# SparkFun-NEO-F9P.net
KiCad netlist of a schematic drawn in EAGLE
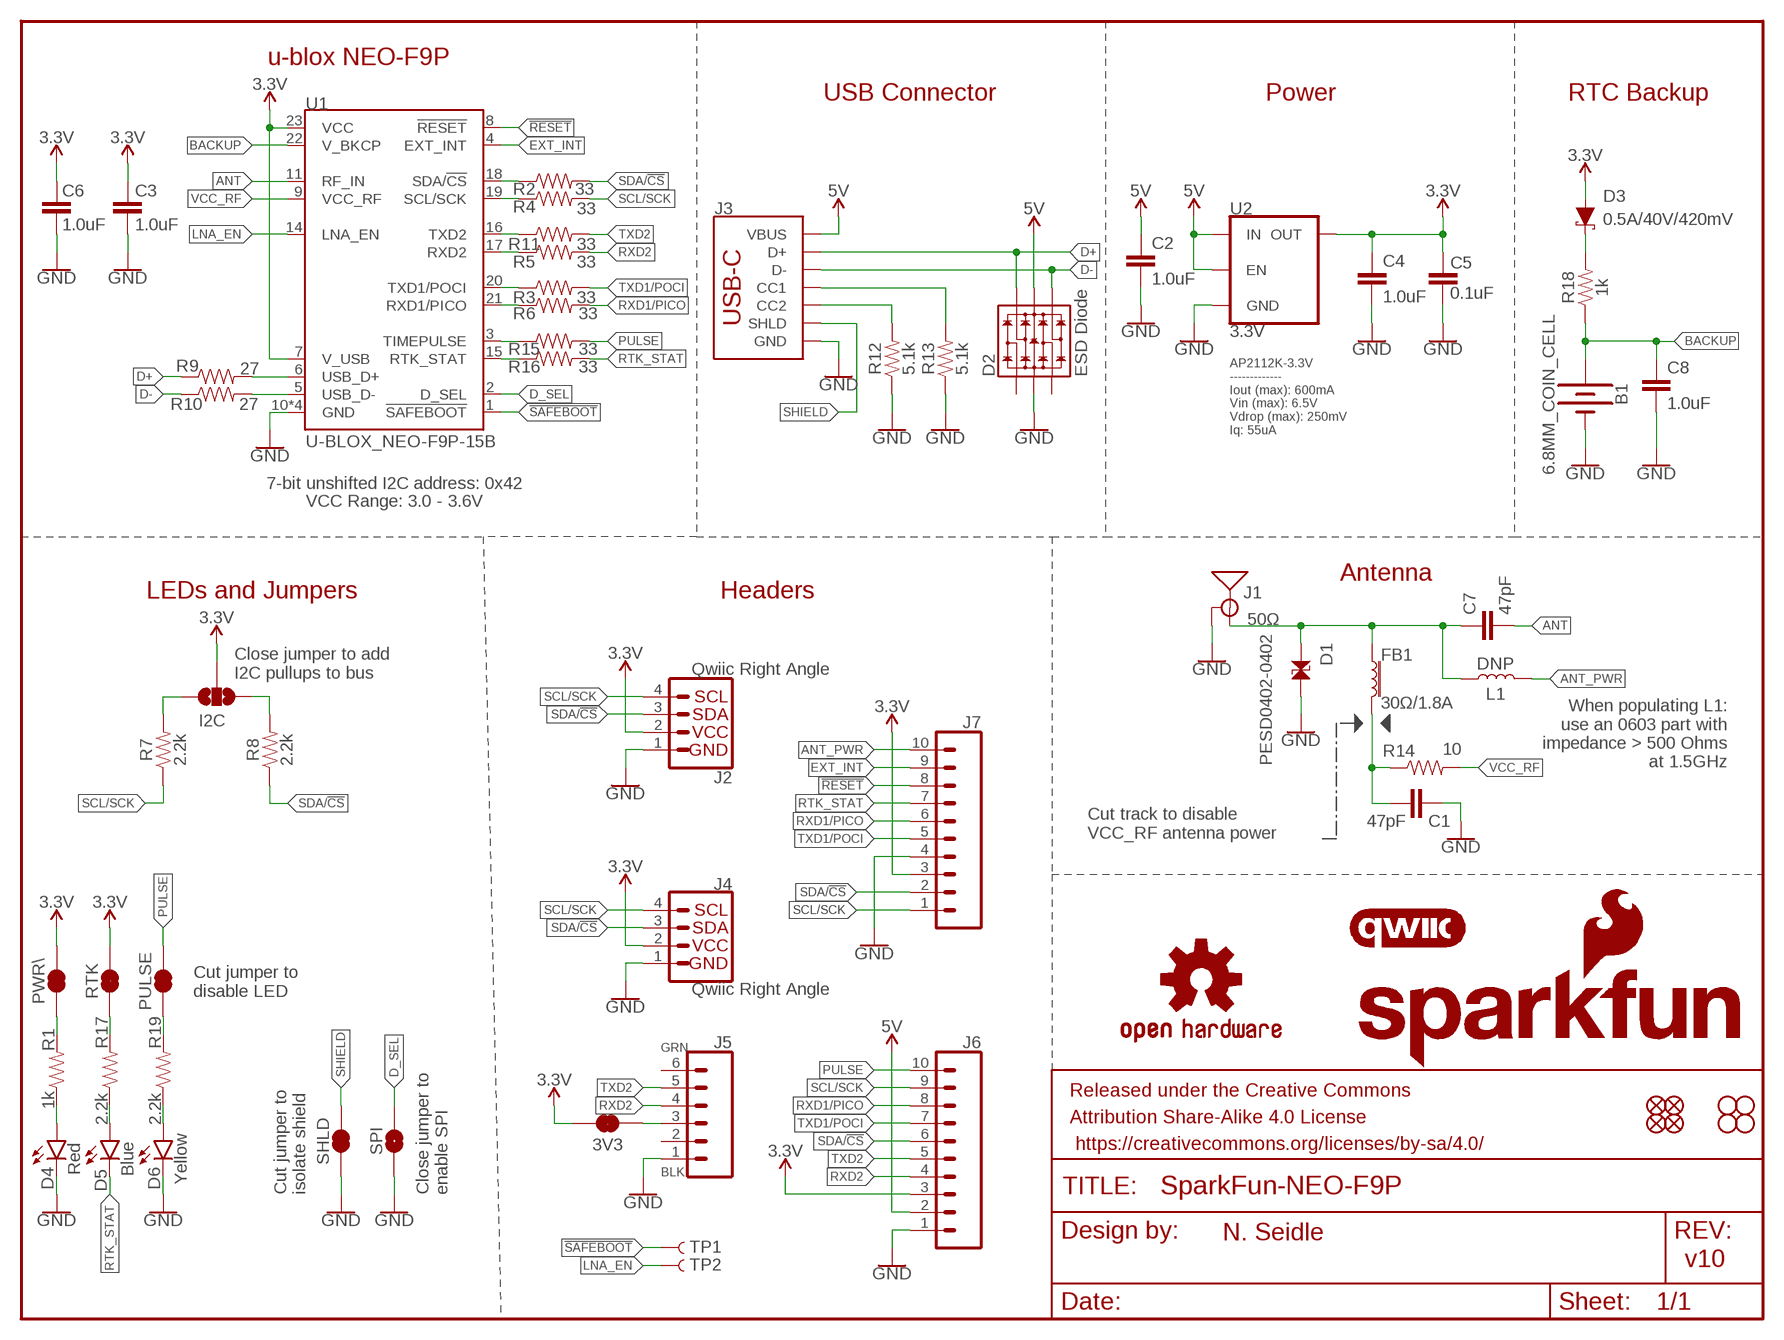
[diagram p0: schematic, sheet 1]

(export (version "E")
  (design (tool "Eeschema 10.0.6"))
  (components
    (comp (ref "3V3")
      (value "JUMPER-SMT_2_NC_TRACE_SILK")
      (footprint "eagle-import:SMT-JUMPER_2_NC_TRACE_SILK")
      (libsource (lib "eagle-import") (part "JUMPER-SMT_2_NC_TRACE_SILK"))
    )
    (comp (ref "B1")
      (value "6.8MM_COIN_CELL")
      (footprint "eagle-import:ML414H_IV01E")
      (libsource (lib "eagle-import") (part "ML414H_IV01E_BATTERY"))
    )
    (comp (ref "C1")
      (value "47pF")
      (footprint "eagle-import:0603")
      (libsource (lib "eagle-import") (part "47PF-0603-50V-5%"))
    )
    (comp (ref "C2")
      (value "1.0uF")
      (footprint "eagle-import:0603")
      (libsource (lib "eagle-import") (part "1.0UF-0603-16V-10%"))
    )
    (comp (ref "C3")
      (value "1.0uF")
      (footprint "eagle-import:0603")
      (libsource (lib "eagle-import") (part "1.0UF-0603-16V-10%"))
    )
    (comp (ref "C4")
      (value "1.0uF")
      (footprint "eagle-import:0603")
      (libsource (lib "eagle-import") (part "1.0UF-0603-16V-10%"))
    )
    (comp (ref "C5")
      (value "0.1uF")
      (footprint "eagle-import:0603")
      (libsource (lib "eagle-import") (part "0.1UF-0603-25V-(+80/-20%)"))
    )
    (comp (ref "C6")
      (value "1.0uF")
      (footprint "eagle-import:0603")
      (libsource (lib "eagle-import") (part "1.0UF-0603-16V-10%"))
    )
    (comp (ref "C7")
      (value "47pF")
      (footprint "eagle-import:0603")
      (libsource (lib "eagle-import") (part "47PF-0603-50V-5%"))
    )
    (comp (ref "C8")
      (value "1.0uF")
      (footprint "eagle-import:0603")
      (libsource (lib "eagle-import") (part "1.0UF-0603-16V-10%-X7R"))
    )
    (comp (ref "D1")
      (value "PESD0402-0402")
      (footprint "eagle-import:0402")
      (fields
        (field (name "DIGIKEY_PART") "PESD0402-140CT-ND")
        (field (name "MOUSE_PART") "650-PESD0402-140")
      )
      (libsource (lib "eagle-import") (part "PESD0402-0402"))
    )
    (comp (ref "D2")
      (value "ESD Diode")
      (footprint "eagle-import:SOT-23-6")
      (libsource (lib "eagle-import") (part "TVS_DIODE_ARRAY_DT1042-04SO-7"))
    )
    (comp (ref "D3")
      (value "0.5A/40V/420mV")
      (footprint "eagle-import:SOD-323")
      (libsource (lib "eagle-import") (part "DIODE-SCHOTTKY-PMEG4005EJ"))
    )
    (comp (ref "D4")
      (value "Red")
      (footprint "eagle-import:LED-0603")
      (libsource (lib "eagle-import") (part "LED-RED0603"))
    )
    (comp (ref "D5")
      (value "Blue")
      (footprint "eagle-import:LED-0603")
      (libsource (lib "eagle-import") (part "LED-BLUE0603"))
    )
    (comp (ref "D6")
      (value "Yellow")
      (footprint "eagle-import:LED-0603")
      (libsource (lib "eagle-import") (part "LED-YELLOW0603"))
    )
    (comp (ref "FB1")
      (value "30Ω/1.8A")
      (footprint "eagle-import:0603")
      (libsource (lib "eagle-import") (part "FERRITE_BEAD-0603"))
    )
    (comp (ref "FRAME1")
      (value "FRAME-LETTER")
      (footprint "eagle-import:CREATIVE_COMMONS")
      (libsource (lib "eagle-import") (part "FRAME-LETTER"))
    )
    (comp (ref "I2C")
      (value "JUMPER-SMT_3_NO_SILK")
      (footprint "eagle-import:SMT-JUMPER_3_NO_SILK")
      (libsource (lib "eagle-import") (part "JUMPER-SMT_3_NO_SILK"))
    )
    (comp (ref "J1")
      (value "ANTENNA-SMA-GROUNDEDEDGE_SMA")
      (footprint "eagle-import:SMA-EDGE")
      (libsource (lib "eagle-import") (part "ANTENNA-SMA-GROUNDEDEDGE_SMA"))
    )
    (comp (ref "J2")
      (value "Qwiic Right Angle")
      (footprint "eagle-import:JST04_1MM_RA")
      (libsource (lib "eagle-import") (part "I2C_STANDARDQWIIC"))
    )
    (comp (ref "J3")
      (value "USB_C_2-LAYER_PADS")
      (footprint "eagle-import:USB-C-16P-2LAYER-PADS")
      (libsource (lib "eagle-import") (part "USB_C_2-LAYER_PADS"))
    )
    (comp (ref "J4")
      (value "Qwiic Right Angle")
      (footprint "eagle-import:JST04_1MM_RA")
      (libsource (lib "eagle-import") (part "I2C_STANDARDQWIIC"))
    )
    (comp (ref "J5")
      (value "CONN_06NO_SILK_FEMALE_PTH")
      (footprint "eagle-import:1X06_NO_SILK")
      (libsource (lib "eagle-import") (part "CONN_06NO_SILK_FEMALE_PTH"))
    )
    (comp (ref "J6")
      (value "CONN_10NO_SILK_PTH_FEMALE")
      (footprint "eagle-import:1X10_NO_SILK")
      (libsource (lib "eagle-import") (part "CONN_10NO_SILK_PTH_FEMALE"))
    )
    (comp (ref "J7")
      (value "CONN_10NO_SILK_PTH_FEMALE")
      (footprint "eagle-import:1X10_NO_SILK")
      (libsource (lib "eagle-import") (part "CONN_10NO_SILK_PTH_FEMALE"))
    )
    (comp (ref "JP21")
      (value "FIDUCIALUFIDUCIAL")
      (footprint "eagle-import:MICRO-FIDUCIAL")
      (libsource (lib "eagle-import") (part "FIDUCIALUFIDUCIAL"))
    )
    (comp (ref "JP31")
      (value "STAND-OFF")
      (footprint "eagle-import:STAND-OFF")
      (libsource (lib "eagle-import") (part "STAND-OFF"))
    )
    (comp (ref "JP41")
      (value "STAND-OFF")
      (footprint "eagle-import:STAND-OFF")
      (libsource (lib "eagle-import") (part "STAND-OFF"))
    )
    (comp (ref "JP61")
      (value "FIDUCIALUFIDUCIAL")
      (footprint "eagle-import:MICRO-FIDUCIAL")
      (libsource (lib "eagle-import") (part "FIDUCIALUFIDUCIAL"))
    )
    (comp (ref "JP71")
      (value "FIDUCIALUFIDUCIAL")
      (footprint "eagle-import:MICRO-FIDUCIAL")
      (libsource (lib "eagle-import") (part "FIDUCIALUFIDUCIAL"))
    )
    (comp (ref "JP81")
      (value "FIDUCIALUFIDUCIAL")
      (footprint "eagle-import:MICRO-FIDUCIAL")
      (libsource (lib "eagle-import") (part "FIDUCIALUFIDUCIAL"))
    )
    (comp (ref "JP91")
      (value "STAND-OFF")
      (footprint "eagle-import:STAND-OFF")
      (libsource (lib "eagle-import") (part "STAND-OFF"))
    )
    (comp (ref "JP101")
      (value "STAND-OFF")
      (footprint "eagle-import:STAND-OFF")
      (libsource (lib "eagle-import") (part "STAND-OFF"))
    )
    (comp (ref "L1")
      (value "DNP")
      (footprint "eagle-import:0603_NO-CREAM")
      (libsource (lib "eagle-import") (part "DNP-0603_NO-CREAM"))
    )
    (comp (ref "LOGO2")
      (value "SFE_LOGO_NAME_FLAME.1_INCH")
      (footprint "eagle-import:SFE_LOGO_NAME_FLAME_.1")
      (libsource (lib "eagle-import") (part "SFE_LOGO_NAME_FLAME.1_INCH"))
    )
    (comp (ref "LOGO3")
      (value "SFE_LOGO_NAME_FLAME7_MM")
      (footprint "eagle-import:SFE_LOGO_NAME_FLAME_7MM")
      (libsource (lib "eagle-import") (part "SFE_LOGO_NAME_FLAME7_MM"))
    )
    (comp (ref "LOGO4")
      (value "OSHW-LOGOS")
      (footprint "eagle-import:OSHW-LOGO-S")
      (libsource (lib "eagle-import") (part "OSHW-LOGOS"))
    )
    (comp (ref "LOGO5")
      (value "QWIIC_LOGO_5MM")
      (footprint "eagle-import:QWIIC_5MM")
      (libsource (lib "eagle-import") (part "QWIIC_LOGO_5MM"))
    )
    (comp (ref "PULSE")
      (value "JUMPER-SMT_2_NC_TRACE_SILK")
      (footprint "eagle-import:SMT-JUMPER_2_NC_TRACE_SILK")
      (libsource (lib "eagle-import") (part "JUMPER-SMT_2_NC_TRACE_SILK"))
    )
    (comp (ref "PWR\\")
      (value "JUMPER-SMT_2_NC_TRACE_SILK")
      (footprint "eagle-import:SMT-JUMPER_2_NC_TRACE_SILK")
      (libsource (lib "eagle-import") (part "JUMPER-SMT_2_NC_TRACE_SILK"))
    )
    (comp (ref "R1")
      (value "1k")
      (footprint "eagle-import:0603")
      (libsource (lib "eagle-import") (part "1KOHM-0603-1/10W-1%"))
    )
    (comp (ref "R2")
      (value "33")
      (footprint "eagle-import:0603")
      (libsource (lib "eagle-import") (part "33OHM-0603-1/10W-1%"))
    )
    (comp (ref "R3")
      (value "33")
      (footprint "eagle-import:0603")
      (libsource (lib "eagle-import") (part "33OHM-0603-1/10W-1%"))
    )
    (comp (ref "R4")
      (value "33")
      (footprint "eagle-import:0603")
      (libsource (lib "eagle-import") (part "33OHM-0603-1/10W-1%"))
    )
    (comp (ref "R5")
      (value "33")
      (footprint "eagle-import:0603")
      (libsource (lib "eagle-import") (part "33OHM-0603-1/10W-1%"))
    )
    (comp (ref "R6")
      (value "33")
      (footprint "eagle-import:0603")
      (libsource (lib "eagle-import") (part "33OHM-0603-1/10W-1%"))
    )
    (comp (ref "R7")
      (value "2.2k")
      (footprint "eagle-import:0603")
      (libsource (lib "eagle-import") (part "2.2KOHM-0603-1/10W-1%"))
    )
    (comp (ref "R8")
      (value "2.2k")
      (footprint "eagle-import:0603")
      (libsource (lib "eagle-import") (part "2.2KOHM-0603-1/10W-1%"))
    )
    (comp (ref "R9")
      (value "27")
      (footprint "eagle-import:0603")
      (libsource (lib "eagle-import") (part "27OHM-0603-1/10W-1%"))
    )
    (comp (ref "R10")
      (value "27")
      (footprint "eagle-import:0603")
      (libsource (lib "eagle-import") (part "27OHM-0603-1/10W-1%"))
    )
    (comp (ref "R11")
      (value "33")
      (footprint "eagle-import:0603")
      (libsource (lib "eagle-import") (part "33OHM-0603-1/10W-1%"))
    )
    (comp (ref "R12")
      (value "5.1k")
      (footprint "eagle-import:0603")
      (libsource (lib "eagle-import") (part "5.1KOHM5.1KOHM-0603-1/10W-1%"))
    )
    (comp (ref "R13")
      (value "5.1k")
      (footprint "eagle-import:0603")
      (libsource (lib "eagle-import") (part "5.1KOHM5.1KOHM-0603-1/10W-1%"))
    )
    (comp (ref "R14")
      (value "10")
      (footprint "eagle-import:0603")
      (libsource (lib "eagle-import") (part "10OHM-0603-1/10W-1%"))
    )
    (comp (ref "R15")
      (value "33")
      (footprint "eagle-import:0603")
      (libsource (lib "eagle-import") (part "33OHM-0603-1/10W-1%"))
    )
    (comp (ref "R16")
      (value "33")
      (footprint "eagle-import:0603")
      (libsource (lib "eagle-import") (part "33OHM-0603-1/10W-1%"))
    )
    (comp (ref "R17")
      (value "2.2k")
      (footprint "eagle-import:0603")
      (libsource (lib "eagle-import") (part "2.2KOHM-0603-1/10W-1%"))
    )
    (comp (ref "R18")
      (value "1k")
      (footprint "eagle-import:0603")
      (libsource (lib "eagle-import") (part "1KOHM-0603-1/10W-1%"))
    )
    (comp (ref "R19")
      (value "2.2k")
      (footprint "eagle-import:0603")
      (libsource (lib "eagle-import") (part "2.2KOHM-0603-1/10W-1%"))
    )
    (comp (ref "RTK")
      (value "JUMPER-SMT_2_NC_TRACE_SILK")
      (footprint "eagle-import:SMT-JUMPER_2_NC_TRACE_SILK")
      (libsource (lib "eagle-import") (part "JUMPER-SMT_2_NC_TRACE_SILK"))
    )
    (comp (ref "SHLD")
      (value "JUMPER-SMT_2_NC_TRACE_SILK")
      (footprint "eagle-import:SMT-JUMPER_2_NC_TRACE_SILK")
      (libsource (lib "eagle-import") (part "JUMPER-SMT_2_NC_TRACE_SILK"))
    )
    (comp (ref "SPI")
      (value "JUMPER-SMT_2_NO_SILK")
      (footprint "eagle-import:SMT-JUMPER_2_NO_SILK")
      (libsource (lib "eagle-import") (part "JUMPER-SMT_2_NO_SILK"))
    )
    (comp (ref "TP1")
      (value "TEST-POINTPOGO_PTH")
      (footprint "eagle-import:1X01_NO_SILK")
      (libsource (lib "eagle-import") (part "TEST-POINTPOGO_PTH"))
    )
    (comp (ref "TP2")
      (value "TEST-POINTPOGO_PTH")
      (footprint "eagle-import:1X01_NO_SILK")
      (libsource (lib "eagle-import") (part "TEST-POINTPOGO_PTH"))
    )
    (comp (ref "U1")
      (value "U-BLOX_NEO-F9P-15B")
      (footprint "eagle-import:NEO-M9N_M8T_M8U_D9S_F9P")
      (libsource (lib "eagle-import") (part "U-BLOX_NEO-F9P-15B"))
    )
    (comp (ref "U2")
      (value "3.3V")
      (footprint "eagle-import:SOT23-5")
      (libsource (lib "eagle-import") (part "V_REG_AP2112K-3.3V"))
    )
  )
  (nets
    (net (code "1") (name "/SDA{slash}~{CS}") (class "Default")
      (node (ref "J2") (pin "3") (pinfunction "3_3") (pintype "passive"))
      (node (ref "J4") (pin "3") (pinfunction "3_3") (pintype "passive"))
      (node (ref "J6") (pin "6") (pinfunction "6_6") (pintype "passive"))
      (node (ref "J7") (pin "2") (pinfunction "2_2") (pintype "passive"))
      (node (ref "R2") (pin "2") (pinfunction "2_2") (pintype "passive"))
      (node (ref "R8") (pin "1") (pinfunction "1_1") (pintype "passive"))
    )
    (net (code "2") (name "/~{RESET}") (class "Default")
      (node (ref "J7") (pin "8") (pinfunction "8_8") (pintype "passive"))
      (node (ref "U1") (pin "8") (pinfunction "~{RESET}_8") (pintype "input"))
    )
    (net (code "3") (name "/~{SAFEBOOT}") (class "Default")
      (node (ref "TP1") (pin "1") (pinfunction "1_1") (pintype "bidirectional"))
      (node (ref "U1") (pin "1") (pinfunction "~{SAFEBOOT}_1") (pintype "input"))
    )
    (net (code "4") (name "3.3V") (class "Default")
      (node (ref "3V3") (pin "2") (pinfunction "2_2") (pintype "passive"))
      (node (ref "C3") (pin "1") (pinfunction "1_1") (pintype "passive"))
      (node (ref "C4") (pin "1") (pinfunction "1_1") (pintype "passive"))
      (node (ref "C5") (pin "2") (pinfunction "2_2") (pintype "passive"))
      (node (ref "C6") (pin "1") (pinfunction "1_1") (pintype "passive"))
      (node (ref "D3") (pin "A") (pinfunction "A_A") (pintype "passive"))
      (node (ref "I2C") (pin "2") (pinfunction "2_2") (pintype "passive"))
      (node (ref "J2") (pin "2") (pinfunction "2_2") (pintype "power_in"))
      (node (ref "J4") (pin "2") (pinfunction "2_2") (pintype "power_in"))
      (node (ref "J6") (pin "3") (pinfunction "3_3") (pintype "passive"))
      (node (ref "J7") (pin "3") (pinfunction "3_3") (pintype "passive"))
      (node (ref "PWR\\") (pin "2") (pinfunction "2_2") (pintype "passive"))
      (node (ref "RTK") (pin "2") (pinfunction "2_2") (pintype "passive"))
      (node (ref "U1") (pin "23") (pinfunction "VCC_23") (pintype "power_in"))
      (node (ref "U1") (pin "7") (pinfunction "V_USB_7") (pintype "power_in"))
      (node (ref "U2") (pin "5") (pinfunction "OUT_5") (pintype "passive"))
    )
    (net (code "5") (name "5V") (class "Default")
      (node (ref "C2") (pin "1") (pinfunction "1_1") (pintype "passive"))
      (node (ref "D2") (pin "5") (pinfunction "VCC_5") (pintype "bidirectional"))
      (node (ref "J3") (pin "VBUS1") (pinfunction "VBUS_VBUS1") (pintype "bidirectional"))
      (node (ref "J3") (pin "VBUS2") (pinfunction "VBUS_VBUS2") (pintype "bidirectional"))
      (node (ref "J6") (pin "2") (pinfunction "2_2") (pintype "passive"))
      (node (ref "U2") (pin "1") (pinfunction "IN_1") (pintype "input"))
      (node (ref "U2") (pin "3") (pinfunction "EN_3") (pintype "input"))
    )
    (net (code "6") (name "ANT") (class "Default")
      (node (ref "C7") (pin "2") (pinfunction "2_2") (pintype "passive"))
      (node (ref "U1") (pin "11") (pinfunction "RF_IN_11") (pintype "input"))
    )
    (net (code "7") (name "ANT_PWR") (class "Default")
      (node (ref "J7") (pin "10") (pinfunction "10_10") (pintype "passive"))
      (node (ref "L1") (pin "2") (pinfunction "2_2") (pintype "passive"))
    )
    (net (code "8") (name "BACKUP") (class "Default")
      (node (ref "B1") (pin "+") (pinfunction "+_+") (pintype "power_in"))
      (node (ref "C8") (pin "1") (pinfunction "1_1") (pintype "passive"))
      (node (ref "R18") (pin "1") (pinfunction "1_1") (pintype "passive"))
      (node (ref "U1") (pin "22") (pinfunction "V_BKCP_22") (pintype "power_in"))
    )
    (net (code "9") (name "D+") (class "Default")
      (node (ref "D2") (pin "6") (pinfunction "IO4_6") (pintype "bidirectional"))
      (node (ref "J3") (pin "A6") (pinfunction "D+_A6") (pintype "bidirectional"))
      (node (ref "J3") (pin "B6") (pinfunction "D+_B6") (pintype "bidirectional"))
      (node (ref "R9") (pin "1") (pinfunction "1_1") (pintype "passive"))
    )
    (net (code "10") (name "D-") (class "Default")
      (node (ref "D2") (pin "4") (pinfunction "IO3_4") (pintype "bidirectional"))
      (node (ref "J3") (pin "A7") (pinfunction "D-_A7") (pintype "bidirectional"))
      (node (ref "J3") (pin "B7") (pinfunction "D-_B7") (pintype "bidirectional"))
      (node (ref "R10") (pin "1") (pinfunction "1_1") (pintype "passive"))
    )
    (net (code "11") (name "D_SEL") (class "Default")
      (node (ref "SPI") (pin "2") (pinfunction "2_2") (pintype "passive"))
      (node (ref "U1") (pin "2") (pinfunction "D_SEL_2") (pintype "input"))
    )
    (net (code "12") (name "EXT_INT") (class "Default")
      (node (ref "J7") (pin "9") (pinfunction "9_9") (pintype "passive"))
      (node (ref "U1") (pin "4") (pinfunction "EXT_INT_4") (pintype "input"))
    )
    (net (code "13") (name "GND") (class "Default")
      (node (ref "B1") (pin "-") (pinfunction "-_-") (pintype "power_in"))
      (node (ref "C1") (pin "2") (pinfunction "2_2") (pintype "passive"))
      (node (ref "C2") (pin "2") (pinfunction "2_2") (pintype "passive"))
      (node (ref "C3") (pin "2") (pinfunction "2_2") (pintype "passive"))
      (node (ref "C4") (pin "2") (pinfunction "2_2") (pintype "passive"))
      (node (ref "C5") (pin "1") (pinfunction "1_1") (pintype "passive"))
      (node (ref "C6") (pin "2") (pinfunction "2_2") (pintype "passive"))
      (node (ref "C8") (pin "2") (pinfunction "2_2") (pintype "passive"))
      (node (ref "D1") (pin "2") (pinfunction "2_2") (pintype "bidirectional"))
      (node (ref "D2") (pin "2") (pinfunction "VSS_2") (pintype "bidirectional"))
      (node (ref "D4") (pin "C") (pinfunction "C_C") (pintype "passive"))
      (node (ref "D6") (pin "C") (pinfunction "C_C") (pintype "passive"))
      (node (ref "J1") (pin "GND@0") (pinfunction "GND_GND@0") (pintype "bidirectional"))
      (node (ref "J1") (pin "GND@1") (pinfunction "GND_GND@1") (pintype "bidirectional"))
      (node (ref "J1") (pin "GND@2") (pinfunction "GND_GND@2") (pintype "bidirectional"))
      (node (ref "J1") (pin "GND@3") (pinfunction "GND_GND@3") (pintype "bidirectional"))
      (node (ref "J2") (pin "1") (pinfunction "1_1") (pintype "power_in"))
      (node (ref "J3") (pin "GND") (pinfunction "GND_GND") (pintype "bidirectional"))
      (node (ref "J3") (pin "GND2") (pinfunction "GND_GND2") (pintype "bidirectional"))
      (node (ref "J4") (pin "1") (pinfunction "1_1") (pintype "power_in"))
      (node (ref "J5") (pin "1") (pinfunction "1_1") (pintype "passive"))
      (node (ref "J6") (pin "1") (pinfunction "1_1") (pintype "passive"))
      (node (ref "J7") (pin "4") (pinfunction "4_4") (pintype "passive"))
      (node (ref "R12") (pin "1") (pinfunction "1_1") (pintype "passive"))
      (node (ref "R13") (pin "1") (pinfunction "1_1") (pintype "passive"))
      (node (ref "SHLD") (pin "1") (pinfunction "1_1") (pintype "passive"))
      (node (ref "SPI") (pin "1") (pinfunction "1_1") (pintype "passive"))
      (node (ref "U1") (pin "10") (pinfunction "GND_10") (pintype "power_in"))
      (node (ref "U1") (pin "12") (pinfunction "GND_12") (pintype "power_in"))
      (node (ref "U1") (pin "13") (pinfunction "GND_13") (pintype "power_in"))
      (node (ref "U1") (pin "24") (pinfunction "GND_24") (pintype "power_in"))
      (node (ref "U2") (pin "2") (pinfunction "GND_2") (pintype "input"))
    )
    (net (code "14") (name "LNA_EN") (class "Default")
      (node (ref "TP2") (pin "1") (pinfunction "1_1") (pintype "bidirectional"))
      (node (ref "U1") (pin "14") (pinfunction "LNA_EN_14") (pintype "output"))
    )
    (net (code "15") (name "Net-(3V3-Pad1)") (class "Default")
      (node (ref "3V3") (pin "1") (pinfunction "1_1") (pintype "passive"))
      (node (ref "J5") (pin "3") (pinfunction "3_3") (pintype "passive"))
    )
    (net (code "16") (name "Net-(C1-Pad1)") (class "Default")
      (node (ref "C1") (pin "1") (pinfunction "1_1") (pintype "passive"))
      (node (ref "FB1") (pin "2") (pinfunction "2_2") (pintype "passive"))
      (node (ref "R14") (pin "1") (pinfunction "1_1") (pintype "passive"))
    )
    (net (code "17") (name "Net-(D3-PadC)") (class "Default")
      (node (ref "D3") (pin "C") (pinfunction "C_C") (pintype "passive"))
      (node (ref "R18") (pin "2") (pinfunction "2_2") (pintype "passive"))
    )
    (net (code "18") (name "Net-(D4-PadA)") (class "Default")
      (node (ref "D4") (pin "A") (pinfunction "A_A") (pintype "passive"))
      (node (ref "R1") (pin "1") (pinfunction "1_1") (pintype "passive"))
    )
    (net (code "19") (name "Net-(D5-PadA)") (class "Default")
      (node (ref "D5") (pin "A") (pinfunction "A_A") (pintype "passive"))
      (node (ref "R17") (pin "1") (pinfunction "1_1") (pintype "passive"))
    )
    (net (code "20") (name "Net-(D6-PadA)") (class "Default")
      (node (ref "D6") (pin "A") (pinfunction "A_A") (pintype "passive"))
      (node (ref "R19") (pin "1") (pinfunction "1_1") (pintype "passive"))
    )
    (net (code "21") (name "Net-(I2C-Pad1)") (class "Default")
      (node (ref "I2C") (pin "1") (pinfunction "1_1") (pintype "passive"))
      (node (ref "R8") (pin "2") (pinfunction "2_2") (pintype "passive"))
    )
    (net (code "22") (name "Net-(I2C-Pad3)") (class "Default")
      (node (ref "I2C") (pin "3") (pinfunction "3_3") (pintype "passive"))
      (node (ref "R7") (pin "2") (pinfunction "2_2") (pintype "passive"))
    )
    (net (code "23") (name "Net-(J1-SIGNAL)") (class "Default")
      (node (ref "C7") (pin "1") (pinfunction "1_1") (pintype "passive"))
      (node (ref "D1") (pin "1") (pinfunction "1_1") (pintype "bidirectional"))
      (node (ref "FB1") (pin "1") (pinfunction "1_1") (pintype "passive"))
      (node (ref "J1") (pin "SIG") (pinfunction "SIGNAL_SIG") (pintype "bidirectional"))
      (node (ref "L1") (pin "1") (pinfunction "1_1") (pintype "passive"))
    )
    (net (code "24") (name "Net-(J3-CC1)") (class "Default")
      (node (ref "J3") (pin "A5") (pinfunction "CC1_A5") (pintype "bidirectional"))
      (node (ref "R13") (pin "2") (pinfunction "2_2") (pintype "passive"))
    )
    (net (code "25") (name "Net-(J3-CC2)") (class "Default")
      (node (ref "J3") (pin "B5") (pinfunction "CC2_B5") (pintype "bidirectional"))
      (node (ref "R12") (pin "2") (pinfunction "2_2") (pintype "passive"))
    )
    (net (code "26") (name "Net-(PULSE-Pad1)") (class "Default")
      (node (ref "PULSE") (pin "1") (pinfunction "1_1") (pintype "passive"))
      (node (ref "R19") (pin "2") (pinfunction "2_2") (pintype "passive"))
    )
    (net (code "27") (name "Net-(PWR\\-Pad1)") (class "Default")
      (node (ref "PWR\\") (pin "1") (pinfunction "1_1") (pintype "passive"))
      (node (ref "R1") (pin "2") (pinfunction "2_2") (pintype "passive"))
    )
    (net (code "28") (name "Net-(R17-Pad2)") (class "Default")
      (node (ref "R17") (pin "2") (pinfunction "2_2") (pintype "passive"))
      (node (ref "RTK") (pin "1") (pinfunction "1_1") (pintype "passive"))
    )
    (net (code "29") (name "Net-(U1-RTK_STAT)") (class "Default")
      (node (ref "R16") (pin "1") (pinfunction "1_1") (pintype "passive"))
      (node (ref "U1") (pin "15") (pinfunction "RTK_STAT_15") (pintype "input"))
    )
    (net (code "30") (name "Net-(U1-RXD1{slash}PICO)") (class "Default")
      (node (ref "R6") (pin "1") (pinfunction "1_1") (pintype "passive"))
      (node (ref "U1") (pin "21") (pinfunction "RXD1/PICO_21") (pintype "input"))
    )
    (net (code "31") (name "Net-(U1-RXD2)") (class "Default")
      (node (ref "R5") (pin "1") (pinfunction "1_1") (pintype "passive"))
      (node (ref "U1") (pin "17") (pinfunction "RXD2_17") (pintype "input"))
    )
    (net (code "32") (name "Net-(U1-SCL{slash}SCK)") (class "Default")
      (node (ref "R4") (pin "1") (pinfunction "1_1") (pintype "passive"))
      (node (ref "U1") (pin "19") (pinfunction "SCL/SCK_19") (pintype "bidirectional"))
    )
    (net (code "33") (name "Net-(U1-SDA{slash}~{CS})") (class "Default")
      (node (ref "R2") (pin "1") (pinfunction "1_1") (pintype "passive"))
      (node (ref "U1") (pin "18") (pinfunction "SDA/~{CS}_18") (pintype "bidirectional"))
    )
    (net (code "34") (name "Net-(U1-TIMEPULSE)") (class "Default")
      (node (ref "R15") (pin "1") (pinfunction "1_1") (pintype "passive"))
      (node (ref "U1") (pin "3") (pinfunction "TIMEPULSE_3") (pintype "output"))
    )
    (net (code "35") (name "Net-(U1-TXD1{slash}POCI)") (class "Default")
      (node (ref "R3") (pin "1") (pinfunction "1_1") (pintype "passive"))
      (node (ref "U1") (pin "20") (pinfunction "TXD1/POCI_20") (pintype "output"))
    )
    (net (code "36") (name "Net-(U1-TXD2)") (class "Default")
      (node (ref "R11") (pin "1") (pinfunction "1_1") (pintype "passive"))
      (node (ref "U1") (pin "16") (pinfunction "TXD2_16") (pintype "output"))
    )
    (net (code "37") (name "Net-(U1-USB_D+)") (class "Default")
      (node (ref "R9") (pin "2") (pinfunction "2_2") (pintype "passive"))
      (node (ref "U1") (pin "6") (pinfunction "USB_D+_6") (pintype "bidirectional"))
    )
    (net (code "38") (name "Net-(U1-USB_D-)") (class "Default")
      (node (ref "R10") (pin "2") (pinfunction "2_2") (pintype "passive"))
      (node (ref "U1") (pin "5") (pinfunction "USB_D-_5") (pintype "bidirectional"))
    )
    (net (code "39") (name "PULSE") (class "Default")
      (node (ref "J6") (pin "10") (pinfunction "10_10") (pintype "passive"))
      (node (ref "PULSE") (pin "2") (pinfunction "2_2") (pintype "passive"))
      (node (ref "R15") (pin "2") (pinfunction "2_2") (pintype "passive"))
    )
    (net (code "40") (name "RTK_STAT") (class "Default")
      (node (ref "D5") (pin "C") (pinfunction "C_C") (pintype "passive"))
      (node (ref "J7") (pin "7") (pinfunction "7_7") (pintype "passive"))
      (node (ref "R16") (pin "2") (pinfunction "2_2") (pintype "passive"))
    )
    (net (code "41") (name "RXD1{slash}PICO") (class "Default")
      (node (ref "J6") (pin "8") (pinfunction "8_8") (pintype "passive"))
      (node (ref "J7") (pin "6") (pinfunction "6_6") (pintype "passive"))
      (node (ref "R6") (pin "2") (pinfunction "2_2") (pintype "passive"))
    )
    (net (code "42") (name "RXD2") (class "Default")
      (node (ref "J5") (pin "4") (pinfunction "4_4") (pintype "passive"))
      (node (ref "J6") (pin "4") (pinfunction "4_4") (pintype "passive"))
      (node (ref "R5") (pin "2") (pinfunction "2_2") (pintype "passive"))
    )
    (net (code "43") (name "SCL{slash}SCK") (class "Default")
      (node (ref "J2") (pin "4") (pinfunction "4_4") (pintype "passive"))
      (node (ref "J4") (pin "4") (pinfunction "4_4") (pintype "passive"))
      (node (ref "J6") (pin "9") (pinfunction "9_9") (pintype "passive"))
      (node (ref "J7") (pin "1") (pinfunction "1_1") (pintype "passive"))
      (node (ref "R4") (pin "2") (pinfunction "2_2") (pintype "passive"))
      (node (ref "R7") (pin "1") (pinfunction "1_1") (pintype "passive"))
    )
    (net (code "44") (name "SHIELD") (class "Default")
      (node (ref "J3") (pin "SHLD1") (pinfunction "SHLD_SHLD1") (pintype "bidirectional"))
      (node (ref "J3") (pin "SHLD2") (pinfunction "SHLD_SHLD2") (pintype "bidirectional"))
      (node (ref "J3") (pin "SHLD3") (pinfunction "SHLD_SHLD3") (pintype "bidirectional"))
      (node (ref "J3") (pin "SHLD4") (pinfunction "SHLD_SHLD4") (pintype "bidirectional"))
      (node (ref "SHLD") (pin "2") (pinfunction "2_2") (pintype "passive"))
    )
    (net (code "45") (name "TXD1{slash}POCI") (class "Default")
      (node (ref "J6") (pin "7") (pinfunction "7_7") (pintype "passive"))
      (node (ref "J7") (pin "5") (pinfunction "5_5") (pintype "passive"))
      (node (ref "R3") (pin "2") (pinfunction "2_2") (pintype "passive"))
    )
    (net (code "46") (name "TXD2") (class "Default")
      (node (ref "J5") (pin "5") (pinfunction "5_5") (pintype "passive"))
      (node (ref "J6") (pin "5") (pinfunction "5_5") (pintype "passive"))
      (node (ref "R11") (pin "2") (pinfunction "2_2") (pintype "passive"))
    )
    (net (code "47") (name "VCC_RF") (class "Default")
      (node (ref "R14") (pin "2") (pinfunction "2_2") (pintype "passive"))
      (node (ref "U1") (pin "9") (pinfunction "VCC_RF_9") (pintype "output"))
    )
    (net (code "48") (name "unconnected-(D2-IO1-Pad1)") (class "Default")
      (node (ref "D2") (pin "1") (pinfunction "IO1_1") (pintype "bidirectional"))
    )
    (net (code "49") (name "unconnected-(D2-IO2-Pad3)") (class "Default")
      (node (ref "D2") (pin "3") (pinfunction "IO2_3") (pintype "bidirectional"))
    )
    (net (code "50") (name "unconnected-(J5-Pad2)") (class "Default")
      (node (ref "J5") (pin "2") (pinfunction "2_2") (pintype "passive"))
    )
    (net (code "51") (name "unconnected-(J5-Pad6)") (class "Default")
      (node (ref "J5") (pin "6") (pinfunction "6_6") (pintype "passive"))
    )
  )
)
